# MCU02.net
KiCad netlist of a schematic drawn in Altium Designer
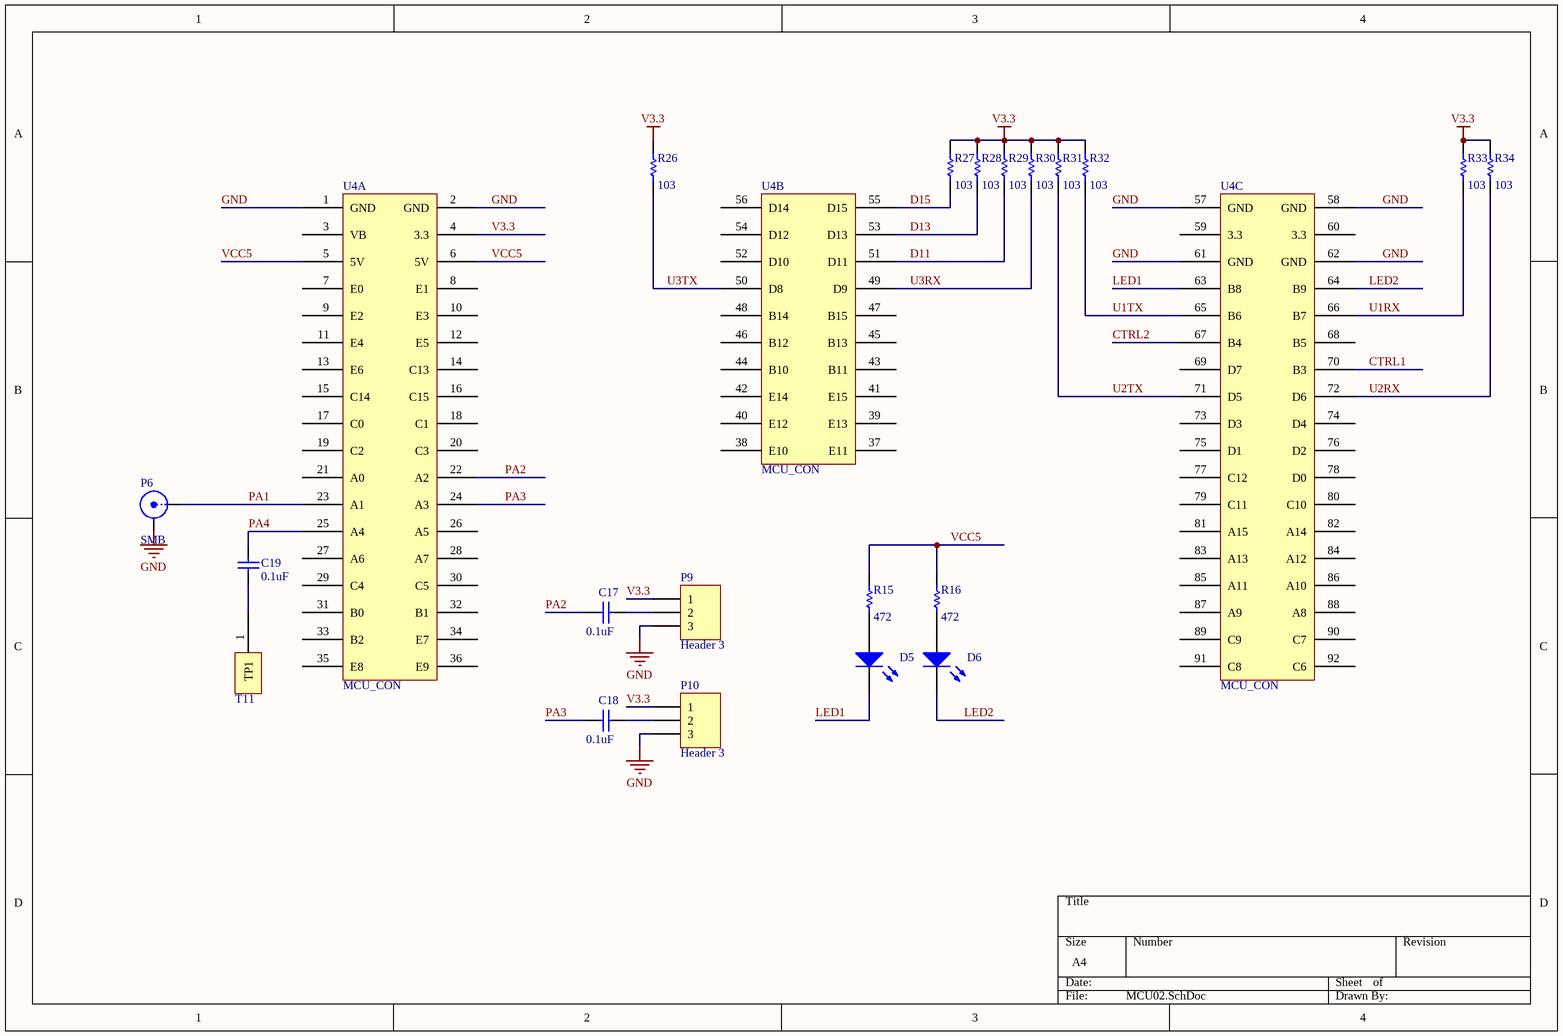
[diagram p0: MCU02.SchDoc]

(export (version "E")
  (design (tool "Eeschema 10.0.6"))
  (components
    (comp (ref "C17")
      (value "0.1uF")
      (description "Capacitor (Semiconductor SIM Model)")
      (fields (field (name "Comment") "Cap Semi") (field (name "PUBLISHER") "Altium Limited"))
      (libsource (lib "Miscellaneous Devices") (part "Cap Semi"))
    )
    (comp (ref "C18")
      (value "0.1uF")
      (description "Capacitor (Semiconductor SIM Model)")
      (fields (field (name "Comment") "Cap Semi") (field (name "PUBLISHER") "Altium Limited"))
      (libsource (lib "Miscellaneous Devices") (part "Cap Semi"))
    )
    (comp (ref "C19")
      (value "0.1uF")
      (description "Capacitor (Semiconductor SIM Model)")
      (fields (field (name "Comment") "Cap Semi") (field (name "PUBLISHER") "Altium Limited"))
      (libsource (lib "Miscellaneous Devices") (part "Cap Semi"))
    )
    (comp (ref "D5")
      (value "LED2")
      (footprint "0805_led")
      (description "Typical RED, GREEN, YELLOW, AMBER GaAs LED")
      (fields (field (name "PUBLISHER") "Altium Limited"))
      (libsource (lib "Miscellaneous Devices") (part "LED2"))
    )
    (comp (ref "D6")
      (value "LED2")
      (footprint "0805_led")
      (description "Typical RED, GREEN, YELLOW, AMBER GaAs LED")
      (fields (field (name "PUBLISHER") "Altium Limited"))
      (libsource (lib "Miscellaneous Devices") (part "LED2"))
    )
    (comp (ref "P6")
      (value "SMB")
      (footprint "SMB_V-RJ45")
      (description "SMB Straight Connector")
      (fields (field (name "PUBLISHER") "Altium Limited"))
      (libsource (lib "Miscellaneous Connectors") (part "SMB"))
    )
    (comp (ref "P9")
      (value "Header 3")
      (footprint "HDR1X3")
      (description "Header, 3-Pin")
      (fields (field (name "PUBLISHER") "Altium Limited"))
      (libsource (lib "Miscellaneous Connectors") (part "Header 3"))
    )
    (comp (ref "P10")
      (value "Header 3")
      (footprint "HDR1X3")
      (description "Header, 3-Pin")
      (fields (field (name "PUBLISHER") "Altium Limited"))
      (libsource (lib "Miscellaneous Connectors") (part "Header 3"))
    )
    (comp (ref "R15")
      (value "472")
      (footprint "1206")
      (description "Semiconductor Resistor")
      (fields (field (name "Comment") "Res Semi") (field (name "PUBLISHER") "Altium Limited"))
      (libsource (lib "Miscellaneous Devices") (part "Res Semi"))
    )
    (comp (ref "R16")
      (value "472")
      (footprint "1206")
      (description "Semiconductor Resistor")
      (fields (field (name "Comment") "Res Semi") (field (name "PUBLISHER") "Altium Limited"))
      (libsource (lib "Miscellaneous Devices") (part "Res Semi"))
    )
    (comp (ref "R26")
      (value "103")
      (footprint "1206")
      (description "Semiconductor Resistor")
      (fields (field (name "Comment") "Res Semi") (field (name "PUBLISHER") "Altium Limited"))
      (libsource (lib "Miscellaneous Devices") (part "Res Semi"))
    )
    (comp (ref "R27")
      (value "103")
      (footprint "1206")
      (description "Semiconductor Resistor")
      (fields (field (name "Comment") "Res Semi") (field (name "PUBLISHER") "Altium Limited"))
      (libsource (lib "Miscellaneous Devices") (part "Res Semi"))
    )
    (comp (ref "R28")
      (value "103")
      (footprint "1206")
      (description "Semiconductor Resistor")
      (fields (field (name "Comment") "Res Semi") (field (name "PUBLISHER") "Altium Limited"))
      (libsource (lib "Miscellaneous Devices") (part "Res Semi"))
    )
    (comp (ref "R29")
      (value "103")
      (footprint "1206")
      (description "Semiconductor Resistor")
      (fields (field (name "Comment") "Res Semi") (field (name "PUBLISHER") "Altium Limited"))
      (libsource (lib "Miscellaneous Devices") (part "Res Semi"))
    )
    (comp (ref "R30")
      (value "103")
      (footprint "1206")
      (description "Semiconductor Resistor")
      (fields (field (name "Comment") "Res Semi") (field (name "PUBLISHER") "Altium Limited"))
      (libsource (lib "Miscellaneous Devices") (part "Res Semi"))
    )
    (comp (ref "R31")
      (value "103")
      (footprint "1206")
      (description "Semiconductor Resistor")
      (fields (field (name "Comment") "Res Semi") (field (name "PUBLISHER") "Altium Limited"))
      (libsource (lib "Miscellaneous Devices") (part "Res Semi"))
    )
    (comp (ref "R32")
      (value "103")
      (footprint "1206")
      (description "Semiconductor Resistor")
      (fields (field (name "Comment") "Res Semi") (field (name "PUBLISHER") "Altium Limited"))
      (libsource (lib "Miscellaneous Devices") (part "Res Semi"))
    )
    (comp (ref "R33")
      (value "103")
      (footprint "1206")
      (description "Semiconductor Resistor")
      (fields (field (name "Comment") "Res Semi") (field (name "PUBLISHER") "Altium Limited"))
      (libsource (lib "Miscellaneous Devices") (part "Res Semi"))
    )
    (comp (ref "R34")
      (value "103")
      (footprint "1206")
      (description "Semiconductor Resistor")
      (fields (field (name "Comment") "Res Semi") (field (name "PUBLISHER") "Altium Limited"))
      (libsource (lib "Miscellaneous Devices") (part "Res Semi"))
    )
    (comp (ref "T11") (value "TP1") (footprint "TP1") (libsource (lib "CHK-I") (part "TP1")))
    (comp (ref "U4") (value "MCU_CON") (footprint "MCU_CON") (libsource (lib "Schlib1") (part "MCU_CON")))
  )
  (nets
    (net (code "1") (name "/CTRL1") (class "Default")
      (node (ref "U4") (pin "70") (pinfunction "B3_70") (pintype "passive"))
    )
    (net (code "2") (name "/CTRL2") (class "Default")
      (node (ref "U4") (pin "67") (pinfunction "B4_67") (pintype "passive"))
    )
    (net (code "3") (name "/D11") (class "Default")
      (node (ref "R29") (pin "1") (pinfunction "1_1") (pintype "passive"))
      (node (ref "U4") (pin "51") (pinfunction "D11_51") (pintype "passive"))
    )
    (net (code "4") (name "/D13") (class "Default")
      (node (ref "R28") (pin "1") (pinfunction "1_1") (pintype "passive"))
      (node (ref "U4") (pin "53") (pinfunction "D13_53") (pintype "passive"))
    )
    (net (code "5") (name "/D15") (class "Default")
      (node (ref "R27") (pin "1") (pinfunction "1_1") (pintype "passive"))
      (node (ref "U4") (pin "55") (pinfunction "D15_55") (pintype "passive"))
    )
    (net (code "6") (name "/LED1") (class "Default")
      (node (ref "D5") (pin "2") (pinfunction "K_2") (pintype "passive"))
      (node (ref "U4") (pin "63") (pinfunction "B8_63") (pintype "passive"))
    )
    (net (code "7") (name "/LED2") (class "Default")
      (node (ref "D6") (pin "2") (pinfunction "K_2") (pintype "passive"))
      (node (ref "U4") (pin "64") (pinfunction "B9_64") (pintype "passive"))
    )
    (net (code "8") (name "/PA1") (class "Default")
      (node (ref "P6") (pin "1") (pinfunction "X_1") (pintype "passive"))
      (node (ref "U4") (pin "23") (pinfunction "A1_23") (pintype "passive"))
    )
    (net (code "9") (name "/PA2") (class "Default")
      (node (ref "C17") (pin "1") (pinfunction "1_1") (pintype "passive"))
      (node (ref "U4") (pin "22") (pinfunction "A2_22") (pintype "passive"))
    )
    (net (code "10") (name "/PA3") (class "Default")
      (node (ref "C18") (pin "1") (pinfunction "1_1") (pintype "passive"))
      (node (ref "U4") (pin "24") (pinfunction "A3_24") (pintype "passive"))
    )
    (net (code "11") (name "/PA4") (class "Default")
      (node (ref "C19") (pin "2") (pinfunction "2_2") (pintype "passive"))
      (node (ref "U4") (pin "25") (pinfunction "A4_25") (pintype "passive"))
    )
    (net (code "12") (name "/U1RX") (class "Default")
      (node (ref "R33") (pin "1") (pinfunction "1_1") (pintype "passive"))
      (node (ref "U4") (pin "66") (pinfunction "B7_66") (pintype "passive"))
    )
    (net (code "13") (name "/U1TX") (class "Default")
      (node (ref "R32") (pin "1") (pinfunction "1_1") (pintype "passive"))
      (node (ref "U4") (pin "65") (pinfunction "B6_65") (pintype "passive"))
    )
    (net (code "14") (name "/U2RX") (class "Default")
      (node (ref "R34") (pin "1") (pinfunction "1_1") (pintype "passive"))
      (node (ref "U4") (pin "72") (pinfunction "D6_72") (pintype "passive"))
    )
    (net (code "15") (name "/U2TX") (class "Default")
      (node (ref "R31") (pin "1") (pinfunction "1_1") (pintype "passive"))
      (node (ref "U4") (pin "71") (pinfunction "D5_71") (pintype "passive"))
    )
    (net (code "16") (name "/U3RX") (class "Default")
      (node (ref "R30") (pin "1") (pinfunction "1_1") (pintype "passive"))
      (node (ref "U4") (pin "49") (pinfunction "D9_49") (pintype "passive"))
    )
    (net (code "17") (name "/U3TX") (class "Default")
      (node (ref "R26") (pin "1") (pinfunction "1_1") (pintype "passive"))
      (node (ref "U4") (pin "50") (pinfunction "D8_50") (pintype "passive"))
    )
    (net (code "18") (name "/VCC5") (class "Default")
      (node (ref "R15") (pin "2") (pinfunction "2_2") (pintype "passive"))
      (node (ref "R16") (pin "2") (pinfunction "2_2") (pintype "passive"))
      (node (ref "U4") (pin "5") (pinfunction "5V_5") (pintype "passive"))
      (node (ref "U4") (pin "6") (pinfunction "5V_6") (pintype "passive"))
    )
    (net (code "19") (name "GND") (class "Default")
      (node (ref "P10") (pin "3") (pinfunction "3_3") (pintype "passive"))
      (node (ref "P6") (pin "2") (pinfunction "Y_2") (pintype "passive"))
      (node (ref "P9") (pin "3") (pinfunction "3_3") (pintype "passive"))
      (node (ref "U4") (pin "1") (pinfunction "GND_1") (pintype "passive"))
      (node (ref "U4") (pin "2") (pinfunction "GND_2") (pintype "passive"))
      (node (ref "U4") (pin "57") (pinfunction "GND_57") (pintype "passive"))
      (node (ref "U4") (pin "58") (pinfunction "GND_58") (pintype "passive"))
      (node (ref "U4") (pin "61") (pinfunction "GND_61") (pintype "passive"))
      (node (ref "U4") (pin "62") (pinfunction "GND_62") (pintype "passive"))
    )
    (net (code "20") (name "Net-(C17-Pad2)") (class "Default")
      (node (ref "C17") (pin "2") (pinfunction "2_2") (pintype "passive"))
      (node (ref "P9") (pin "2") (pinfunction "2_2") (pintype "passive"))
    )
    (net (code "21") (name "Net-(C18-Pad2)") (class "Default")
      (node (ref "C18") (pin "2") (pinfunction "2_2") (pintype "passive"))
      (node (ref "P10") (pin "2") (pinfunction "2_2") (pintype "passive"))
    )
    (net (code "22") (name "Net-(D5-A)") (class "Default")
      (node (ref "D5") (pin "1") (pinfunction "A_1") (pintype "passive"))
      (node (ref "R15") (pin "1") (pinfunction "1_1") (pintype "passive"))
    )
    (net (code "23") (name "Net-(D6-A)") (class "Default")
      (node (ref "D6") (pin "1") (pinfunction "A_1") (pintype "passive"))
      (node (ref "R16") (pin "1") (pinfunction "1_1") (pintype "passive"))
    )
    (net (code "24") (name "Net-(T11-TP1)") (class "Default")
      (node (ref "C19") (pin "1") (pinfunction "1_1") (pintype "passive"))
      (node (ref "T11") (pin "1") (pinfunction "TP1_1") (pintype "passive"))
    )
    (net (code "25") (name "V3.3") (class "Default")
      (node (ref "P10") (pin "1") (pinfunction "1_1") (pintype "passive"))
      (node (ref "P9") (pin "1") (pinfunction "1_1") (pintype "passive"))
      (node (ref "R26") (pin "2") (pinfunction "2_2") (pintype "passive"))
      (node (ref "R27") (pin "2") (pinfunction "2_2") (pintype "passive"))
      (node (ref "R28") (pin "2") (pinfunction "2_2") (pintype "passive"))
      (node (ref "R29") (pin "2") (pinfunction "2_2") (pintype "passive"))
      (node (ref "R30") (pin "2") (pinfunction "2_2") (pintype "passive"))
      (node (ref "R31") (pin "2") (pinfunction "2_2") (pintype "passive"))
      (node (ref "R32") (pin "2") (pinfunction "2_2") (pintype "passive"))
      (node (ref "R33") (pin "2") (pinfunction "2_2") (pintype "passive"))
      (node (ref "R34") (pin "2") (pinfunction "2_2") (pintype "passive"))
      (node (ref "U4") (pin "4") (pinfunction "3.3_4") (pintype "passive"))
    )
    (net (code "26") (name "unconnected-(U4A-A0-Pad21)") (class "Default")
      (node (ref "U4") (pin "21") (pinfunction "A0_21") (pintype "passive"))
    )
    (net (code "27") (name "unconnected-(U4A-A5-Pad26)") (class "Default")
      (node (ref "U4") (pin "26") (pinfunction "A5_26") (pintype "passive"))
    )
    (net (code "28") (name "unconnected-(U4A-A6-Pad27)") (class "Default")
      (node (ref "U4") (pin "27") (pinfunction "A6_27") (pintype "passive"))
    )
    (net (code "29") (name "unconnected-(U4A-A7-Pad28)") (class "Default")
      (node (ref "U4") (pin "28") (pinfunction "A7_28") (pintype "passive"))
    )
    (net (code "30") (name "unconnected-(U4A-B0-Pad31)") (class "Default")
      (node (ref "U4") (pin "31") (pinfunction "B0_31") (pintype "passive"))
    )
    (net (code "31") (name "unconnected-(U4A-B1-Pad32)") (class "Default")
      (node (ref "U4") (pin "32") (pinfunction "B1_32") (pintype "passive"))
    )
    (net (code "32") (name "unconnected-(U4A-B2-Pad33)") (class "Default")
      (node (ref "U4") (pin "33") (pinfunction "B2_33") (pintype "passive"))
    )
    (net (code "33") (name "unconnected-(U4A-C0-Pad17)") (class "Default")
      (node (ref "U4") (pin "17") (pinfunction "C0_17") (pintype "passive"))
    )
    (net (code "34") (name "unconnected-(U4A-C1-Pad18)") (class "Default")
      (node (ref "U4") (pin "18") (pinfunction "C1_18") (pintype "passive"))
    )
    (net (code "35") (name "unconnected-(U4A-C2-Pad19)") (class "Default")
      (node (ref "U4") (pin "19") (pinfunction "C2_19") (pintype "passive"))
    )
    (net (code "36") (name "unconnected-(U4A-C3-Pad20)") (class "Default")
      (node (ref "U4") (pin "20") (pinfunction "C3_20") (pintype "passive"))
    )
    (net (code "37") (name "unconnected-(U4A-C4-Pad29)") (class "Default")
      (node (ref "U4") (pin "29") (pinfunction "C4_29") (pintype "passive"))
    )
    (net (code "38") (name "unconnected-(U4A-C5-Pad30)") (class "Default")
      (node (ref "U4") (pin "30") (pinfunction "C5_30") (pintype "passive"))
    )
    (net (code "39") (name "unconnected-(U4A-C13-Pad14)") (class "Default")
      (node (ref "U4") (pin "14") (pinfunction "C13_14") (pintype "passive"))
    )
    (net (code "40") (name "unconnected-(U4A-C14-Pad15)") (class "Default")
      (node (ref "U4") (pin "15") (pinfunction "C14_15") (pintype "passive"))
    )
    (net (code "41") (name "unconnected-(U4A-C15-Pad16)") (class "Default")
      (node (ref "U4") (pin "16") (pinfunction "C15_16") (pintype "passive"))
    )
    (net (code "42") (name "unconnected-(U4A-E0-Pad7)") (class "Default")
      (node (ref "U4") (pin "7") (pinfunction "E0_7") (pintype "passive"))
    )
    (net (code "43") (name "unconnected-(U4A-E1-Pad8)") (class "Default")
      (node (ref "U4") (pin "8") (pinfunction "E1_8") (pintype "passive"))
    )
    (net (code "44") (name "unconnected-(U4A-E2-Pad9)") (class "Default")
      (node (ref "U4") (pin "9") (pinfunction "E2_9") (pintype "passive"))
    )
    (net (code "45") (name "unconnected-(U4A-E3-Pad10)") (class "Default")
      (node (ref "U4") (pin "10") (pinfunction "E3_10") (pintype "passive"))
    )
    (net (code "46") (name "unconnected-(U4A-E4-Pad11)") (class "Default")
      (node (ref "U4") (pin "11") (pinfunction "E4_11") (pintype "passive"))
    )
    (net (code "47") (name "unconnected-(U4A-E5-Pad12)") (class "Default")
      (node (ref "U4") (pin "12") (pinfunction "E5_12") (pintype "passive"))
    )
    (net (code "48") (name "unconnected-(U4A-E6-Pad13)") (class "Default")
      (node (ref "U4") (pin "13") (pinfunction "E6_13") (pintype "passive"))
    )
    (net (code "49") (name "unconnected-(U4A-E7-Pad34)") (class "Default")
      (node (ref "U4") (pin "34") (pinfunction "E7_34") (pintype "passive"))
    )
    (net (code "50") (name "unconnected-(U4A-E8-Pad35)") (class "Default")
      (node (ref "U4") (pin "35") (pinfunction "E8_35") (pintype "passive"))
    )
    (net (code "51") (name "unconnected-(U4A-E9-Pad36)") (class "Default")
      (node (ref "U4") (pin "36") (pinfunction "E9_36") (pintype "passive"))
    )
    (net (code "52") (name "unconnected-(U4A-VB-Pad3)") (class "Default")
      (node (ref "U4") (pin "3") (pinfunction "VB_3") (pintype "passive"))
    )
    (net (code "53") (name "unconnected-(U4B-B10-Pad44)") (class "Default")
      (node (ref "U4") (pin "44") (pinfunction "B10_44") (pintype "passive"))
    )
    (net (code "54") (name "unconnected-(U4B-B11-Pad43)") (class "Default")
      (node (ref "U4") (pin "43") (pinfunction "B11_43") (pintype "passive"))
    )
    (net (code "55") (name "unconnected-(U4B-B12-Pad46)") (class "Default")
      (node (ref "U4") (pin "46") (pinfunction "B12_46") (pintype "passive"))
    )
    (net (code "56") (name "unconnected-(U4B-B13-Pad45)") (class "Default")
      (node (ref "U4") (pin "45") (pinfunction "B13_45") (pintype "passive"))
    )
    (net (code "57") (name "unconnected-(U4B-B14-Pad48)") (class "Default")
      (node (ref "U4") (pin "48") (pinfunction "B14_48") (pintype "passive"))
    )
    (net (code "58") (name "unconnected-(U4B-B15-Pad47)") (class "Default")
      (node (ref "U4") (pin "47") (pinfunction "B15_47") (pintype "passive"))
    )
    (net (code "59") (name "unconnected-(U4B-D10-Pad52)") (class "Default")
      (node (ref "U4") (pin "52") (pinfunction "D10_52") (pintype "passive"))
    )
    (net (code "60") (name "unconnected-(U4B-D12-Pad54)") (class "Default")
      (node (ref "U4") (pin "54") (pinfunction "D12_54") (pintype "passive"))
    )
    (net (code "61") (name "unconnected-(U4B-D14-Pad56)") (class "Default")
      (node (ref "U4") (pin "56") (pinfunction "D14_56") (pintype "passive"))
    )
    (net (code "62") (name "unconnected-(U4B-E10-Pad38)") (class "Default")
      (node (ref "U4") (pin "38") (pinfunction "E10_38") (pintype "passive"))
    )
    (net (code "63") (name "unconnected-(U4B-E11-Pad37)") (class "Default")
      (node (ref "U4") (pin "37") (pinfunction "E11_37") (pintype "passive"))
    )
    (net (code "64") (name "unconnected-(U4B-E12-Pad40)") (class "Default")
      (node (ref "U4") (pin "40") (pinfunction "E12_40") (pintype "passive"))
    )
    (net (code "65") (name "unconnected-(U4B-E13-Pad39)") (class "Default")
      (node (ref "U4") (pin "39") (pinfunction "E13_39") (pintype "passive"))
    )
    (net (code "66") (name "unconnected-(U4B-E14-Pad42)") (class "Default")
      (node (ref "U4") (pin "42") (pinfunction "E14_42") (pintype "passive"))
    )
    (net (code "67") (name "unconnected-(U4B-E15-Pad41)") (class "Default")
      (node (ref "U4") (pin "41") (pinfunction "E15_41") (pintype "passive"))
    )
    (net (code "68") (name "unconnected-(U4C-3.3-Pad59)") (class "Default")
      (node (ref "U4") (pin "59") (pinfunction "3.3_59") (pintype "passive"))
    )
    (net (code "69") (name "unconnected-(U4C-3.3-Pad60)") (class "Default")
      (node (ref "U4") (pin "60") (pinfunction "3.3_60") (pintype "passive"))
    )
    (net (code "70") (name "unconnected-(U4C-A8-Pad88)") (class "Default")
      (node (ref "U4") (pin "88") (pinfunction "A8_88") (pintype "passive"))
    )
    (net (code "71") (name "unconnected-(U4C-A9-Pad87)") (class "Default")
      (node (ref "U4") (pin "87") (pinfunction "A9_87") (pintype "passive"))
    )
    (net (code "72") (name "unconnected-(U4C-A10-Pad86)") (class "Default")
      (node (ref "U4") (pin "86") (pinfunction "A10_86") (pintype "passive"))
    )
    (net (code "73") (name "unconnected-(U4C-A11-Pad85)") (class "Default")
      (node (ref "U4") (pin "85") (pinfunction "A11_85") (pintype "passive"))
    )
    (net (code "74") (name "unconnected-(U4C-A12-Pad84)") (class "Default")
      (node (ref "U4") (pin "84") (pinfunction "A12_84") (pintype "passive"))
    )
    (net (code "75") (name "unconnected-(U4C-A13-Pad83)") (class "Default")
      (node (ref "U4") (pin "83") (pinfunction "A13_83") (pintype "passive"))
    )
    (net (code "76") (name "unconnected-(U4C-A14-Pad82)") (class "Default")
      (node (ref "U4") (pin "82") (pinfunction "A14_82") (pintype "passive"))
    )
    (net (code "77") (name "unconnected-(U4C-A15-Pad81)") (class "Default")
      (node (ref "U4") (pin "81") (pinfunction "A15_81") (pintype "passive"))
    )
    (net (code "78") (name "unconnected-(U4C-B5-Pad68)") (class "Default")
      (node (ref "U4") (pin "68") (pinfunction "B5_68") (pintype "passive"))
    )
    (net (code "79") (name "unconnected-(U4C-C6-Pad92)") (class "Default")
      (node (ref "U4") (pin "92") (pinfunction "C6_92") (pintype "passive"))
    )
    (net (code "80") (name "unconnected-(U4C-C7-Pad90)") (class "Default")
      (node (ref "U4") (pin "90") (pinfunction "C7_90") (pintype "passive"))
    )
    (net (code "81") (name "unconnected-(U4C-C8-Pad91)") (class "Default")
      (node (ref "U4") (pin "91") (pinfunction "C8_91") (pintype "passive"))
    )
    (net (code "82") (name "unconnected-(U4C-C9-Pad89)") (class "Default")
      (node (ref "U4") (pin "89") (pinfunction "C9_89") (pintype "passive"))
    )
    (net (code "83") (name "unconnected-(U4C-C10-Pad80)") (class "Default")
      (node (ref "U4") (pin "80") (pinfunction "C10_80") (pintype "passive"))
    )
    (net (code "84") (name "unconnected-(U4C-C11-Pad79)") (class "Default")
      (node (ref "U4") (pin "79") (pinfunction "C11_79") (pintype "passive"))
    )
    (net (code "85") (name "unconnected-(U4C-C12-Pad77)") (class "Default")
      (node (ref "U4") (pin "77") (pinfunction "C12_77") (pintype "passive"))
    )
    (net (code "86") (name "unconnected-(U4C-D0-Pad78)") (class "Default")
      (node (ref "U4") (pin "78") (pinfunction "D0_78") (pintype "passive"))
    )
    (net (code "87") (name "unconnected-(U4C-D1-Pad75)") (class "Default")
      (node (ref "U4") (pin "75") (pinfunction "D1_75") (pintype "passive"))
    )
    (net (code "88") (name "unconnected-(U4C-D2-Pad76)") (class "Default")
      (node (ref "U4") (pin "76") (pinfunction "D2_76") (pintype "passive"))
    )
    (net (code "89") (name "unconnected-(U4C-D3-Pad73)") (class "Default")
      (node (ref "U4") (pin "73") (pinfunction "D3_73") (pintype "passive"))
    )
    (net (code "90") (name "unconnected-(U4C-D4-Pad74)") (class "Default")
      (node (ref "U4") (pin "74") (pinfunction "D4_74") (pintype "passive"))
    )
    (net (code "91") (name "unconnected-(U4C-D7-Pad69)") (class "Default")
      (node (ref "U4") (pin "69") (pinfunction "D7_69") (pintype "passive"))
    )
  )
)
